# 12-6v.net
KiCad netlist of a schematic drawn in Altium Designer
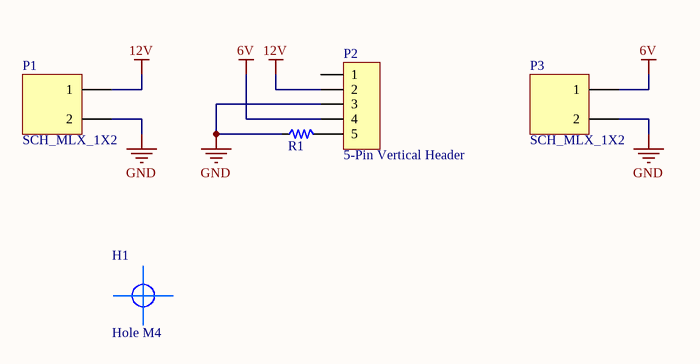
[diagram p0: 12-6v.SchDoc]

(export (version "E")
  (design (tool "Eeschema 10.0.6"))
  (components
    (comp (ref "H1") (value "Hole M4") (footprint "#10Hole") (libsource (lib "#10Hole") (part "#10Hole")))
    (comp (ref "P1")
      (value "SCH_MLX_1X2")
      (footprint "PCB_MLX_MICROFIT_1X2")
      (libsource (lib "Molex Microfit 3.0 1x2") (part "SCH_MLX_1X2"))
    )
    (comp (ref "P2")
      (value "5-Pin Vertical Header")
      (footprint "5-Pin Vertical Header")
      (fields (field (name "MANUFACTURER") "Sullins"))
      (libsource (lib "5 Pin 100 mil Vertical Header - Through Hole") (part "5-Pin Vertical Header"))
    )
    (comp (ref "P3")
      (value "SCH_MLX_1X2")
      (footprint "PCB_MLX_MICROFIT_1X2")
      (libsource (lib "Molex Microfit 3.0 1x2") (part "SCH_MLX_1X2"))
    )
    (comp (ref "R1")
      (value "SCH_GENERIC_RESISTOR_0603")
      (footprint "PCB_GENERIC_SMD_0603")
      (description "Generic SMD resistor 0603")
      (libsource (lib "Generic 0603 Resistor") (part "SCH_GENERIC_RESISTOR_0603"))
    )
  )
  (nets
    (net (code "1") (name "6V") (class "Default")
      (node (ref "P2") (pin "4") (pinfunction "4_4") (pintype "passive"))
      (node (ref "P3") (pin "1") (pinfunction "1_1") (pintype "passive"))
    )
    (net (code "2") (name "12V") (class "Default")
      (node (ref "P1") (pin "1") (pinfunction "1_1") (pintype "passive"))
      (node (ref "P2") (pin "2") (pinfunction "2_2") (pintype "passive"))
    )
    (net (code "3") (name "GND") (class "Default")
      (node (ref "P1") (pin "2") (pinfunction "2_2") (pintype "passive"))
      (node (ref "P2") (pin "3") (pinfunction "3_3") (pintype "passive"))
      (node (ref "P3") (pin "2") (pinfunction "2_2") (pintype "passive"))
      (node (ref "R1") (pin "1") (pinfunction "1_1") (pintype "passive"))
    )
    (net (code "4") (name "Net-(P2-Pad5)") (class "Default")
      (node (ref "P2") (pin "5") (pinfunction "5_5") (pintype "passive"))
      (node (ref "R1") (pin "2") (pinfunction "2_2") (pintype "passive"))
    )
    (net (code "5") (name "unconnected-(P2-Pad1)") (class "Default")
      (node (ref "P2") (pin "1") (pinfunction "1_1") (pintype "passive"))
    )
  )
)
